# taurus_v1.net
KiCad netlist of a schematic drawn in EAGLE
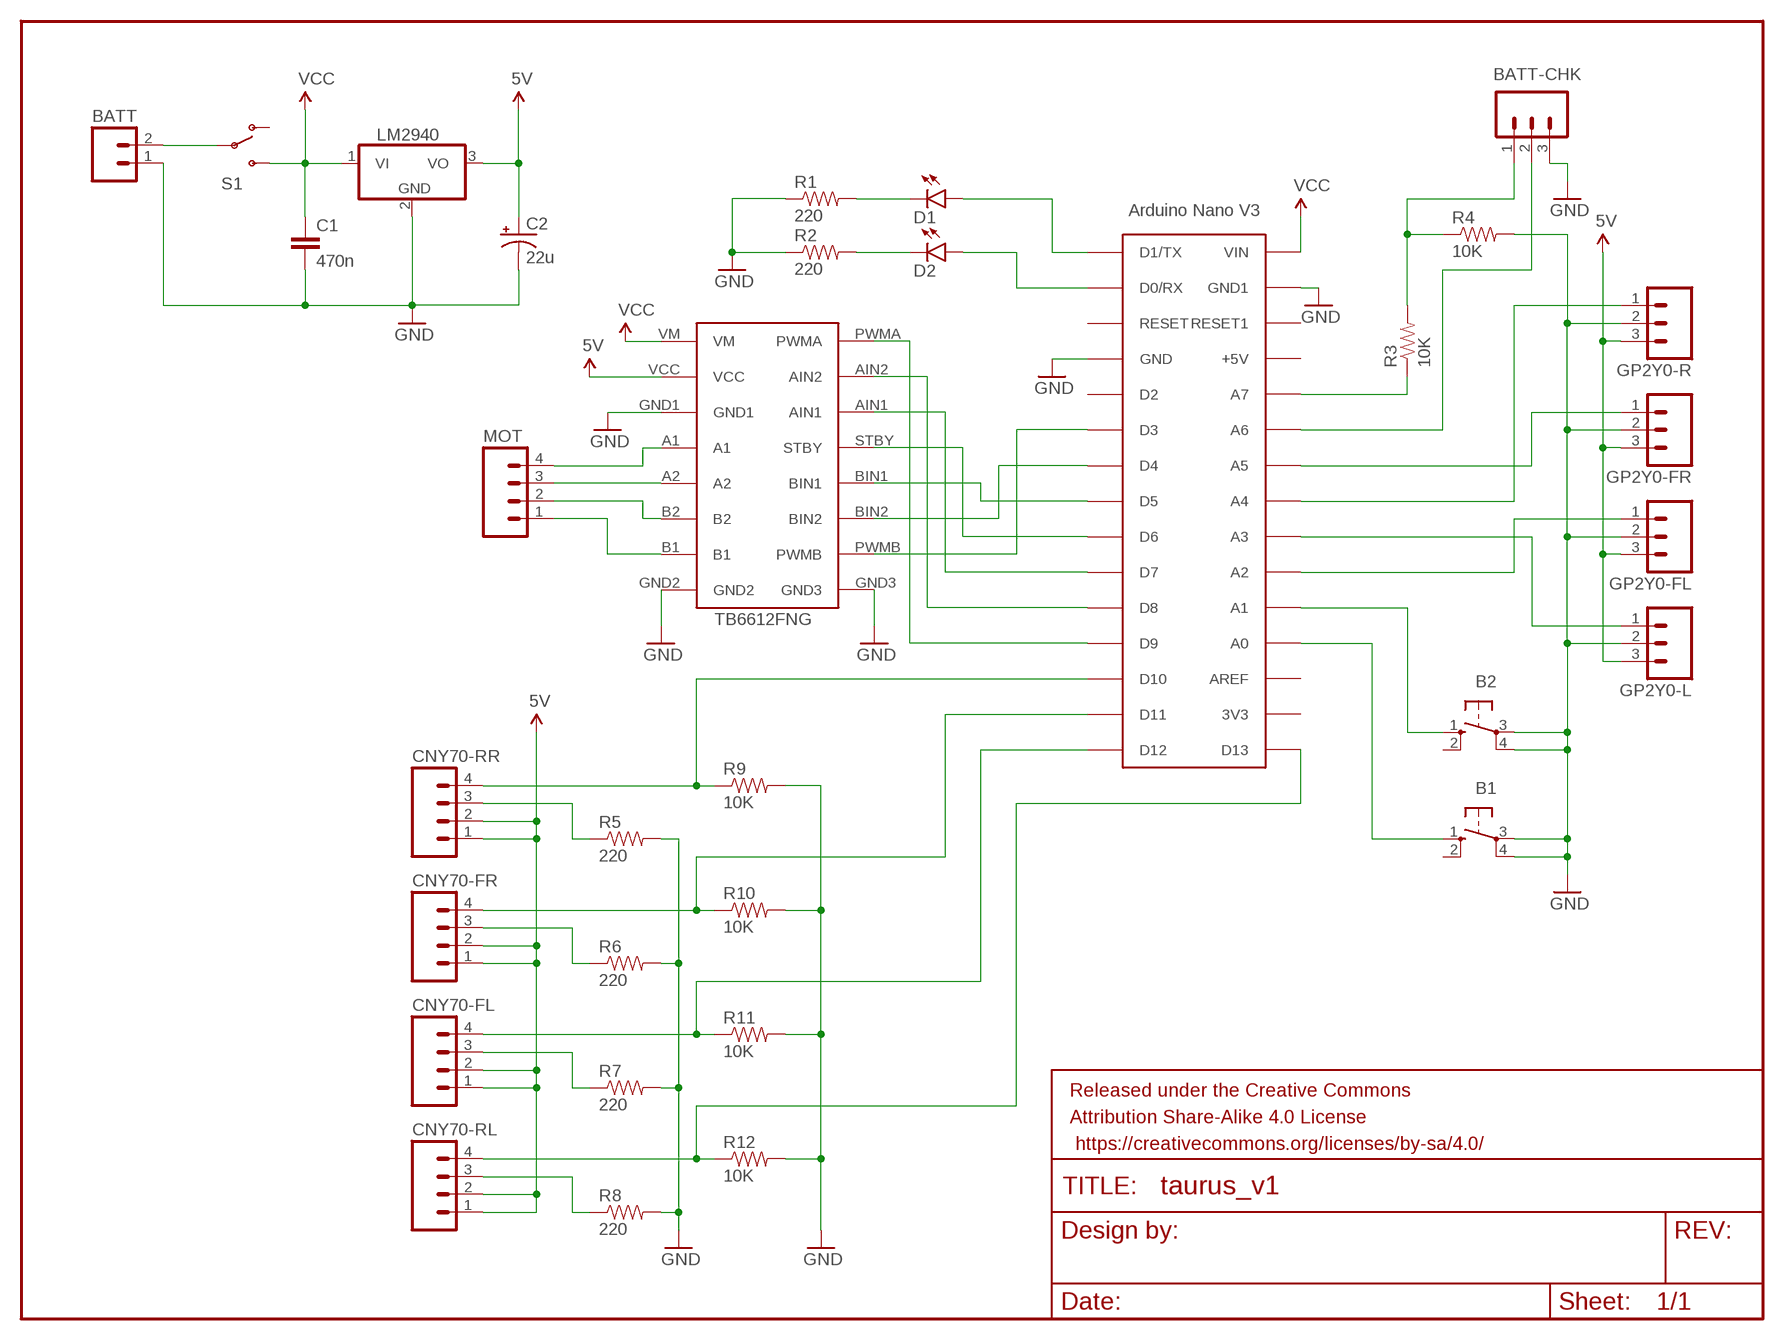
[diagram p0: schematic, sheet 1]

(export (version "E")
  (design (tool "Eeschema 10.0.6"))
  (components
    (comp (ref "B1")
      (value "10-XX")
      (footprint "eagle-import:B3F-10XX")
      (fields (field (name "MPN") "B3F-1000"))
      (libsource (lib "eagle-import") (part "10-XX"))
    )
    (comp (ref "B2")
      (value "10-XX")
      (footprint "eagle-import:B3F-10XX")
      (fields (field (name "MPN") "B3F-1000"))
      (libsource (lib "eagle-import") (part "10-XX"))
    )
    (comp (ref "BATT")
      (value "M02PTH")
      (footprint "eagle-import:1X02")
      (libsource (lib "eagle-import") (part "M02PTH"))
    )
    (comp (ref "BATT-CHK")
      (value "M03PTH")
      (footprint "eagle-import:1X03")
      (libsource (lib "eagle-import") (part "M03PTH"))
    )
    (comp (ref "C1")
      (value "470n")
      (footprint "eagle-import:CAP-PTH-5MM")
      (libsource (lib "eagle-import") (part "CAPPTH1"))
    )
    (comp (ref "C2")
      (value "22u")
      (footprint "eagle-import:CPOL-RADIAL-10UF-25V")
      (libsource (lib "eagle-import") (part "CAP_POLPTH2"))
    )
    (comp (ref "CNY70-FL")
      (value "M04PTH")
      (footprint "eagle-import:1X04")
      (libsource (lib "eagle-import") (part "M04PTH"))
    )
    (comp (ref "CNY70-FR")
      (value "M04PTH")
      (footprint "eagle-import:1X04")
      (libsource (lib "eagle-import") (part "M04PTH"))
    )
    (comp (ref "CNY70-RL")
      (value "M04PTH")
      (footprint "eagle-import:1X04")
      (libsource (lib "eagle-import") (part "M04PTH"))
    )
    (comp (ref "CNY70-RR")
      (value "M04PTH")
      (footprint "eagle-import:1X04")
      (libsource (lib "eagle-import") (part "M04PTH"))
    )
    (comp (ref "D1")
      (value "LED3MM")
      (footprint "eagle-import:LED3MM")
      (libsource (lib "eagle-import") (part "LED3MM"))
    )
    (comp (ref "D2")
      (value "LED3MM")
      (footprint "eagle-import:LED3MM")
      (libsource (lib "eagle-import") (part "LED3MM"))
    )
    (comp (ref "FRAME1")
      (value "FRAME-LETTERNO_PACKAGE")
      (footprint "eagle-import:DUMMY")
      (fields (field (name "DESIGNER") "Nobody"))
      (libsource (lib "eagle-import") (part "FRAME-LETTERNO_PACKAGE"))
    )
    (comp (ref "GP2Y0-FL")
      (value "M03PTH")
      (footprint "eagle-import:1X03")
      (libsource (lib "eagle-import") (part "M03PTH"))
    )
    (comp (ref "GP2Y0-FR")
      (value "M03PTH")
      (footprint "eagle-import:1X03")
      (libsource (lib "eagle-import") (part "M03PTH"))
    )
    (comp (ref "GP2Y0-L")
      (value "M03PTH")
      (footprint "eagle-import:1X03")
      (libsource (lib "eagle-import") (part "M03PTH"))
    )
    (comp (ref "GP2Y0-R")
      (value "M03PTH")
      (footprint "eagle-import:1X03")
      (libsource (lib "eagle-import") (part "M03PTH"))
    )
    (comp (ref "LM2940")
      (value "7805TV")
      (footprint "eagle-import:TO220V")
      (libsource (lib "eagle-import") (part "78TV05"))
    )
    (comp (ref "MOT")
      (value "M04PTH")
      (footprint "eagle-import:1X04")
      (libsource (lib "eagle-import") (part "M04PTH"))
    )
    (comp (ref "R1")
      (value "220")
      (footprint "eagle-import:AXIAL-0.4")
      (libsource (lib "eagle-import") (part "RESISTORPTH-1/4W"))
    )
    (comp (ref "R2")
      (value "220")
      (footprint "eagle-import:AXIAL-0.4")
      (libsource (lib "eagle-import") (part "RESISTORPTH-1/4W"))
    )
    (comp (ref "R3")
      (value "10K")
      (footprint "eagle-import:AXIAL-0.4")
      (libsource (lib "eagle-import") (part "RESISTORPTH-1/4W"))
    )
    (comp (ref "R4")
      (value "10K")
      (footprint "eagle-import:AXIAL-0.4")
      (libsource (lib "eagle-import") (part "RESISTORPTH-1/4W"))
    )
    (comp (ref "R5")
      (value "220")
      (footprint "eagle-import:AXIAL-0.4")
      (libsource (lib "eagle-import") (part "RESISTORPTH-1/4W"))
    )
    (comp (ref "R6")
      (value "220")
      (footprint "eagle-import:AXIAL-0.4")
      (libsource (lib "eagle-import") (part "RESISTORPTH-1/4W"))
    )
    (comp (ref "R7")
      (value "220")
      (footprint "eagle-import:AXIAL-0.4")
      (libsource (lib "eagle-import") (part "RESISTORPTH-1/4W"))
    )
    (comp (ref "R8")
      (value "220")
      (footprint "eagle-import:AXIAL-0.4")
      (libsource (lib "eagle-import") (part "RESISTORPTH-1/4W"))
    )
    (comp (ref "R9")
      (value "10K")
      (footprint "eagle-import:AXIAL-0.4")
      (libsource (lib "eagle-import") (part "RESISTORPTH-1/4W"))
    )
    (comp (ref "R10")
      (value "10K")
      (footprint "eagle-import:AXIAL-0.4")
      (libsource (lib "eagle-import") (part "RESISTORPTH-1/4W"))
    )
    (comp (ref "R11")
      (value "10K")
      (footprint "eagle-import:AXIAL-0.4")
      (libsource (lib "eagle-import") (part "RESISTORPTH-1/4W"))
    )
    (comp (ref "R12")
      (value "10K")
      (footprint "eagle-import:AXIAL-0.4")
      (libsource (lib "eagle-import") (part "RESISTORPTH-1/4W"))
    )
    (comp (ref "S1")
      (value "SWITCH-SPDTPTH")
      (footprint "eagle-import:SWITCH-SPDT")
      (libsource (lib "eagle-import") (part "SWITCH-SPDTPTH"))
    )
    (comp (ref "TB1")
      (value "TB6612FNG")
      (footprint "eagle-import:TB6612FNG")
      (libsource (lib "eagle-import") (part "TB6612FNG"))
    )
    (comp (ref "U$1")
      (value "ARDUINONANO")
      (footprint "eagle-import:PDIP-32")
      (libsource (lib "eagle-import") (part "ARDUINONANO"))
    )
  )
  (nets
    (net (code "1") (name "5V") (class "Default")
      (node (ref "C2") (pin "1") (pinfunction "+_1") (pintype "passive"))
      (node (ref "CNY70-FL") (pin "1") (pinfunction "1_1") (pintype "passive"))
      (node (ref "CNY70-FL") (pin "2") (pinfunction "2_2") (pintype "passive"))
      (node (ref "CNY70-FR") (pin "1") (pinfunction "1_1") (pintype "passive"))
      (node (ref "CNY70-FR") (pin "2") (pinfunction "2_2") (pintype "passive"))
      (node (ref "CNY70-RL") (pin "1") (pinfunction "1_1") (pintype "passive"))
      (node (ref "CNY70-RL") (pin "2") (pinfunction "2_2") (pintype "passive"))
      (node (ref "CNY70-RR") (pin "1") (pinfunction "1_1") (pintype "passive"))
      (node (ref "CNY70-RR") (pin "2") (pinfunction "2_2") (pintype "passive"))
      (node (ref "GP2Y0-FL") (pin "3") (pinfunction "3_3") (pintype "passive"))
      (node (ref "GP2Y0-FR") (pin "3") (pinfunction "3_3") (pintype "passive"))
      (node (ref "GP2Y0-L") (pin "3") (pinfunction "3_3") (pintype "passive"))
      (node (ref "GP2Y0-R") (pin "3") (pinfunction "3_3") (pintype "passive"))
      (node (ref "LM2940") (pin "3") (pinfunction "VO_3") (pintype "passive"))
      (node (ref "TB1") (pin "VCC") (pinfunction "VCC_VCC") (pintype "bidirectional"))
    )
    (net (code "2") (name "GND") (class "Default")
      (node (ref "B1") (pin "3") (pinfunction "P_3") (pintype "passive"))
      (node (ref "B1") (pin "4") (pinfunction "P1_4") (pintype "passive"))
      (node (ref "B2") (pin "3") (pinfunction "P_3") (pintype "passive"))
      (node (ref "B2") (pin "4") (pinfunction "P1_4") (pintype "passive"))
      (node (ref "BATT") (pin "1") (pinfunction "1_1") (pintype "passive"))
      (node (ref "BATT-CHK") (pin "3") (pinfunction "3_3") (pintype "passive"))
      (node (ref "C1") (pin "2") (pinfunction "2_2") (pintype "passive"))
      (node (ref "C2") (pin "2") (pinfunction "-_2") (pintype "passive"))
      (node (ref "GP2Y0-FL") (pin "2") (pinfunction "2_2") (pintype "passive"))
      (node (ref "GP2Y0-FR") (pin "2") (pinfunction "2_2") (pintype "passive"))
      (node (ref "GP2Y0-L") (pin "2") (pinfunction "2_2") (pintype "passive"))
      (node (ref "GP2Y0-R") (pin "2") (pinfunction "2_2") (pintype "passive"))
      (node (ref "LM2940") (pin "2") (pinfunction "GND_2") (pintype "passive"))
      (node (ref "R1") (pin "P$1") (pinfunction "1_P$1") (pintype "passive"))
      (node (ref "R10") (pin "P$2") (pinfunction "2_P$2") (pintype "passive"))
      (node (ref "R11") (pin "P$2") (pinfunction "2_P$2") (pintype "passive"))
      (node (ref "R12") (pin "P$2") (pinfunction "2_P$2") (pintype "passive"))
      (node (ref "R2") (pin "P$1") (pinfunction "1_P$1") (pintype "passive"))
      (node (ref "R4") (pin "P$2") (pinfunction "2_P$2") (pintype "passive"))
      (node (ref "R5") (pin "P$2") (pinfunction "2_P$2") (pintype "passive"))
      (node (ref "R6") (pin "P$2") (pinfunction "2_P$2") (pintype "passive"))
      (node (ref "R7") (pin "P$2") (pinfunction "2_P$2") (pintype "passive"))
      (node (ref "R8") (pin "P$2") (pinfunction "2_P$2") (pintype "passive"))
      (node (ref "R9") (pin "P$2") (pinfunction "2_P$2") (pintype "passive"))
      (node (ref "TB1") (pin "GND1") (pinfunction "GND1_GND1") (pintype "bidirectional"))
      (node (ref "TB1") (pin "GND2") (pinfunction "GND2_GND2") (pintype "bidirectional"))
      (node (ref "TB1") (pin "GND3") (pinfunction "GND3_GND3") (pintype "bidirectional"))
      (node (ref "U$1") (pin "GND") (pinfunction "GND_GND") (pintype "bidirectional"))
      (node (ref "U$1") (pin "GND1") (pinfunction "GND1_GND1") (pintype "bidirectional"))
    )
    (net (code "3") (name "Net-(B1-S)") (class "Default")
      (node (ref "B1") (pin "1") (pinfunction "S_1") (pintype "passive"))
      (node (ref "U$1") (pin "A7") (pinfunction "A0_A7") (pintype "bidirectional"))
    )
    (net (code "4") (name "Net-(B2-S)") (class "Default")
      (node (ref "B2") (pin "1") (pinfunction "S_1") (pintype "passive"))
      (node (ref "U$1") (pin "A6") (pinfunction "A1_A6") (pintype "bidirectional"))
    )
    (net (code "5") (name "Net-(D1-C)") (class "Default")
      (node (ref "D1") (pin "K") (pinfunction "C_K") (pintype "passive"))
      (node (ref "R1") (pin "P$2") (pinfunction "2_P$2") (pintype "passive"))
    )
    (net (code "6") (name "Net-(D1-PadA)") (class "Default")
      (node (ref "D1") (pin "A") (pinfunction "A_A") (pintype "passive"))
      (node (ref "U$1") (pin "D1/TX") (pinfunction "D1/TX_D1/TX") (pintype "bidirectional"))
    )
    (net (code "7") (name "Net-(D2-C)") (class "Default")
      (node (ref "D2") (pin "K") (pinfunction "C_K") (pintype "passive"))
      (node (ref "R2") (pin "P$2") (pinfunction "2_P$2") (pintype "passive"))
    )
    (net (code "8") (name "Net-(D2-PadA)") (class "Default")
      (node (ref "D2") (pin "A") (pinfunction "A_A") (pintype "passive"))
      (node (ref "U$1") (pin "D0/RX") (pinfunction "D0/RX_D0/RX") (pintype "bidirectional"))
    )
    (net (code "9") (name "Net-(MOT-Pad1)") (class "Default")
      (node (ref "MOT") (pin "1") (pinfunction "1_1") (pintype "passive"))
      (node (ref "TB1") (pin "B1") (pinfunction "B1_B1") (pintype "bidirectional"))
    )
    (net (code "10") (name "Net-(MOT-Pad2)") (class "Default")
      (node (ref "MOT") (pin "2") (pinfunction "2_2") (pintype "passive"))
      (node (ref "TB1") (pin "B2") (pinfunction "B2_B2") (pintype "bidirectional"))
    )
    (net (code "11") (name "Net-(MOT-Pad3)") (class "Default")
      (node (ref "MOT") (pin "3") (pinfunction "3_3") (pintype "passive"))
      (node (ref "TB1") (pin "A2") (pinfunction "A2_A2") (pintype "bidirectional"))
    )
    (net (code "12") (name "Net-(MOT-Pad4)") (class "Default")
      (node (ref "MOT") (pin "4") (pinfunction "4_4") (pintype "passive"))
      (node (ref "TB1") (pin "A1") (pinfunction "A1_A1") (pintype "bidirectional"))
    )
    (net (code "13") (name "Net-(R3-1)") (class "Default")
      (node (ref "R3") (pin "P$1") (pinfunction "1_P$1") (pintype "passive"))
      (node (ref "U$1") (pin "A0") (pinfunction "A7_A0") (pintype "bidirectional"))
    )
    (net (code "14") (name "Net-(R3-2)") (class "Default")
      (node (ref "BATT-CHK") (pin "1") (pinfunction "1_1") (pintype "passive"))
      (node (ref "R3") (pin "P$2") (pinfunction "2_P$2") (pintype "passive"))
      (node (ref "R4") (pin "P$1") (pinfunction "1_P$1") (pintype "passive"))
    )
    (net (code "15") (name "Net-(R5-1)") (class "Default")
      (node (ref "CNY70-RR") (pin "3") (pinfunction "3_3") (pintype "passive"))
      (node (ref "R5") (pin "P$1") (pinfunction "1_P$1") (pintype "passive"))
    )
    (net (code "16") (name "Net-(R6-1)") (class "Default")
      (node (ref "CNY70-FR") (pin "3") (pinfunction "3_3") (pintype "passive"))
      (node (ref "R6") (pin "P$1") (pinfunction "1_P$1") (pintype "passive"))
    )
    (net (code "17") (name "Net-(R7-1)") (class "Default")
      (node (ref "CNY70-FL") (pin "3") (pinfunction "3_3") (pintype "passive"))
      (node (ref "R7") (pin "P$1") (pinfunction "1_P$1") (pintype "passive"))
    )
    (net (code "18") (name "Net-(R8-1)") (class "Default")
      (node (ref "CNY70-RL") (pin "3") (pinfunction "3_3") (pintype "passive"))
      (node (ref "R8") (pin "P$1") (pinfunction "1_P$1") (pintype "passive"))
    )
    (net (code "19") (name "Net-(R9-1)") (class "Default")
      (node (ref "CNY70-RR") (pin "4") (pinfunction "4_4") (pintype "passive"))
      (node (ref "R9") (pin "P$1") (pinfunction "1_P$1") (pintype "passive"))
      (node (ref "U$1") (pin "D10") (pinfunction "D10_D10") (pintype "bidirectional"))
    )
    (net (code "20") (name "Net-(R10-1)") (class "Default")
      (node (ref "CNY70-FR") (pin "4") (pinfunction "4_4") (pintype "passive"))
      (node (ref "R10") (pin "P$1") (pinfunction "1_P$1") (pintype "passive"))
      (node (ref "U$1") (pin "D11") (pinfunction "D11_D11") (pintype "bidirectional"))
    )
    (net (code "21") (name "Net-(R11-1)") (class "Default")
      (node (ref "CNY70-FL") (pin "4") (pinfunction "4_4") (pintype "passive"))
      (node (ref "R11") (pin "P$1") (pinfunction "1_P$1") (pintype "passive"))
      (node (ref "U$1") (pin "D12") (pinfunction "D12_D12") (pintype "bidirectional"))
    )
    (net (code "22") (name "Net-(R12-1)") (class "Default")
      (node (ref "CNY70-RL") (pin "4") (pinfunction "4_4") (pintype "passive"))
      (node (ref "R12") (pin "P$1") (pinfunction "1_P$1") (pintype "passive"))
      (node (ref "U$1") (pin "D13") (pinfunction "D13_D13") (pintype "bidirectional"))
    )
    (net (code "23") (name "Net-(S1-P)") (class "Default")
      (node (ref "BATT") (pin "2") (pinfunction "2_2") (pintype "passive"))
      (node (ref "S1") (pin "2") (pinfunction "P_2") (pintype "passive"))
    )
    (net (code "24") (name "Net-(TB1-PadAIN1)") (class "Default")
      (node (ref "TB1") (pin "AIN1") (pinfunction "AIN1_AIN1") (pintype "bidirectional"))
      (node (ref "U$1") (pin "D7") (pinfunction "D7_D7") (pintype "bidirectional"))
    )
    (net (code "25") (name "Net-(TB1-PadAIN2)") (class "Default")
      (node (ref "TB1") (pin "AIN2") (pinfunction "AIN2_AIN2") (pintype "bidirectional"))
      (node (ref "U$1") (pin "D8") (pinfunction "D8_D8") (pintype "bidirectional"))
    )
    (net (code "26") (name "Net-(TB1-PadBIN1)") (class "Default")
      (node (ref "TB1") (pin "BIN1") (pinfunction "BIN1_BIN1") (pintype "bidirectional"))
      (node (ref "U$1") (pin "D5") (pinfunction "D5_D5") (pintype "bidirectional"))
    )
    (net (code "27") (name "Net-(TB1-PadBIN2)") (class "Default")
      (node (ref "TB1") (pin "BIN2") (pinfunction "BIN2_BIN2") (pintype "bidirectional"))
      (node (ref "U$1") (pin "D4") (pinfunction "D4_D4") (pintype "bidirectional"))
    )
    (net (code "28") (name "Net-(TB1-PadPWMA)") (class "Default")
      (node (ref "TB1") (pin "PWMA") (pinfunction "PWMA_PWMA") (pintype "bidirectional"))
      (node (ref "U$1") (pin "D9") (pinfunction "D9_D9") (pintype "bidirectional"))
    )
    (net (code "29") (name "Net-(TB1-PadPWMB)") (class "Default")
      (node (ref "TB1") (pin "PWMB") (pinfunction "PWMB_PWMB") (pintype "bidirectional"))
      (node (ref "U$1") (pin "D3") (pinfunction "D3_D3") (pintype "bidirectional"))
    )
    (net (code "30") (name "Net-(TB1-PadSTBY)") (class "Default")
      (node (ref "TB1") (pin "STBY") (pinfunction "STBY_STBY") (pintype "bidirectional"))
      (node (ref "U$1") (pin "D6") (pinfunction "D6_D6") (pintype "bidirectional"))
    )
    (net (code "31") (name "Net-(U$1-A2)") (class "Default")
      (node (ref "GP2Y0-FL") (pin "1") (pinfunction "1_1") (pintype "passive"))
      (node (ref "U$1") (pin "A5") (pinfunction "A2_A5") (pintype "bidirectional"))
    )
    (net (code "32") (name "Net-(U$1-A3)") (class "Default")
      (node (ref "GP2Y0-L") (pin "1") (pinfunction "1_1") (pintype "passive"))
      (node (ref "U$1") (pin "A4") (pinfunction "A3_A4") (pintype "bidirectional"))
    )
    (net (code "33") (name "Net-(U$1-A4)") (class "Default")
      (node (ref "GP2Y0-R") (pin "1") (pinfunction "1_1") (pintype "passive"))
      (node (ref "U$1") (pin "A3") (pinfunction "A4_A3") (pintype "bidirectional"))
    )
    (net (code "34") (name "Net-(U$1-A5)") (class "Default")
      (node (ref "GP2Y0-FR") (pin "1") (pinfunction "1_1") (pintype "passive"))
      (node (ref "U$1") (pin "A2") (pinfunction "A5_A2") (pintype "bidirectional"))
    )
    (net (code "35") (name "Net-(U$1-A6)") (class "Default")
      (node (ref "BATT-CHK") (pin "2") (pinfunction "2_2") (pintype "passive"))
      (node (ref "U$1") (pin "A1") (pinfunction "A6_A1") (pintype "bidirectional"))
    )
    (net (code "36") (name "VCC") (class "Default")
      (node (ref "C1") (pin "1") (pinfunction "1_1") (pintype "passive"))
      (node (ref "LM2940") (pin "1") (pinfunction "VI_1") (pintype "input"))
      (node (ref "S1") (pin "3") (pinfunction "S_3") (pintype "passive"))
      (node (ref "TB1") (pin "VM") (pinfunction "VM_VM") (pintype "bidirectional"))
      (node (ref "U$1") (pin "VIN") (pinfunction "VIN_VIN") (pintype "bidirectional"))
    )
    (net (code "37") (name "unconnected-(B1-S1-Pad2)") (class "Default")
      (node (ref "B1") (pin "2") (pinfunction "S1_2") (pintype "passive"))
    )
    (net (code "38") (name "unconnected-(B2-S1-Pad2)") (class "Default")
      (node (ref "B2") (pin "2") (pinfunction "S1_2") (pintype "passive"))
    )
    (net (code "39") (name "unconnected-(S1-O-Pad1)") (class "Default")
      (node (ref "S1") (pin "1") (pinfunction "O_1") (pintype "passive"))
    )
    (net (code "40") (name "unconnected-(U$1-Pad+5V)") (class "Default")
      (node (ref "U$1") (pin "+5V") (pinfunction "+5V_+5V") (pintype "bidirectional"))
    )
    (net (code "41") (name "unconnected-(U$1-Pad3V3)") (class "Default")
      (node (ref "U$1") (pin "3V3") (pinfunction "3V3_3V3") (pintype "bidirectional"))
    )
    (net (code "42") (name "unconnected-(U$1-PadAREF)") (class "Default")
      (node (ref "U$1") (pin "AREF") (pinfunction "AREF_AREF") (pintype "bidirectional"))
    )
    (net (code "43") (name "unconnected-(U$1-PadD2)") (class "Default")
      (node (ref "U$1") (pin "D2") (pinfunction "D2_D2") (pintype "bidirectional"))
    )
    (net (code "44") (name "unconnected-(U$1-PadRESET)") (class "Default")
      (node (ref "U$1") (pin "RESET") (pinfunction "RESET_RESET") (pintype "bidirectional"))
    )
    (net (code "45") (name "unconnected-(U$1-PadRESET1)") (class "Default")
      (node (ref "U$1") (pin "RESET1") (pinfunction "RESET1_RESET1") (pintype "bidirectional"))
    )
  )
)
